# 08_FPGA_banks_3_4_5.net
KiCad netlist of a schematic drawn in Altium Designer
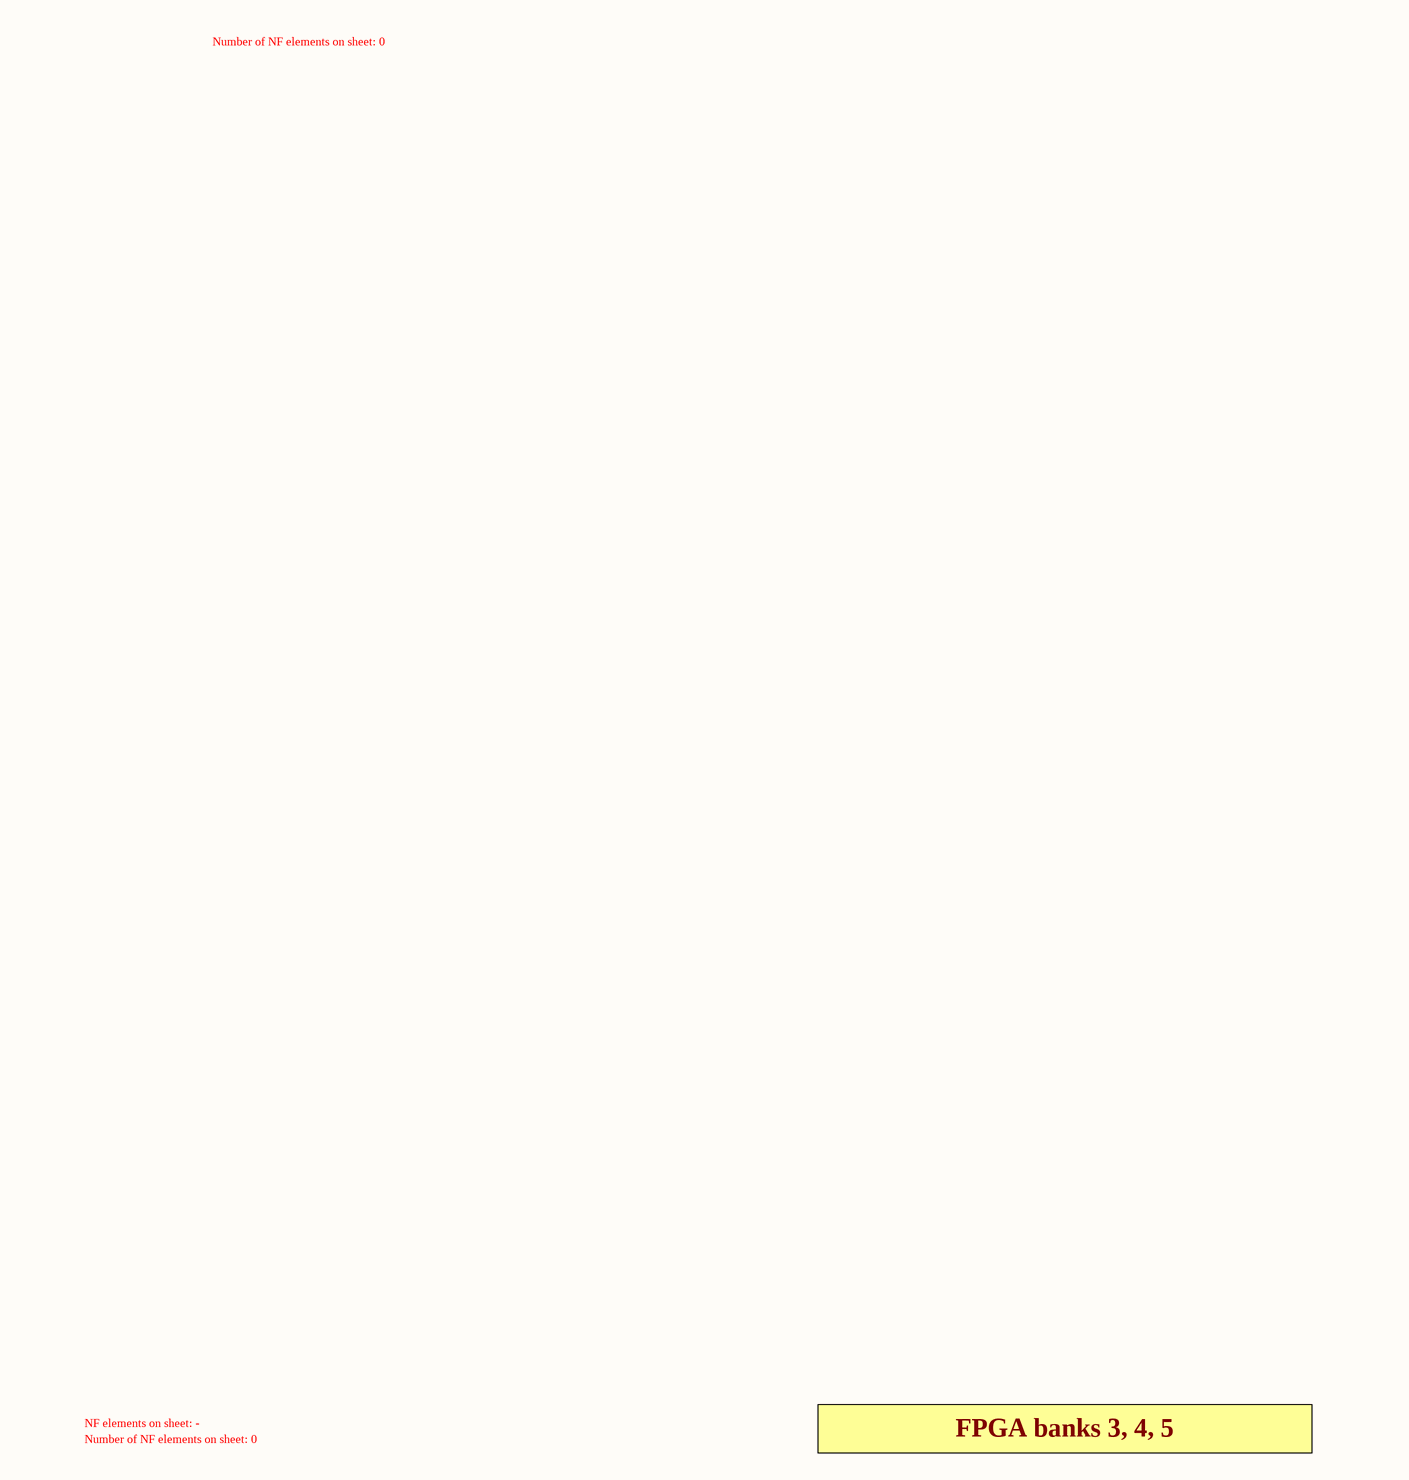
[diagram p0: 08_FPGA_banks_3_4_5.SchDoc, top]
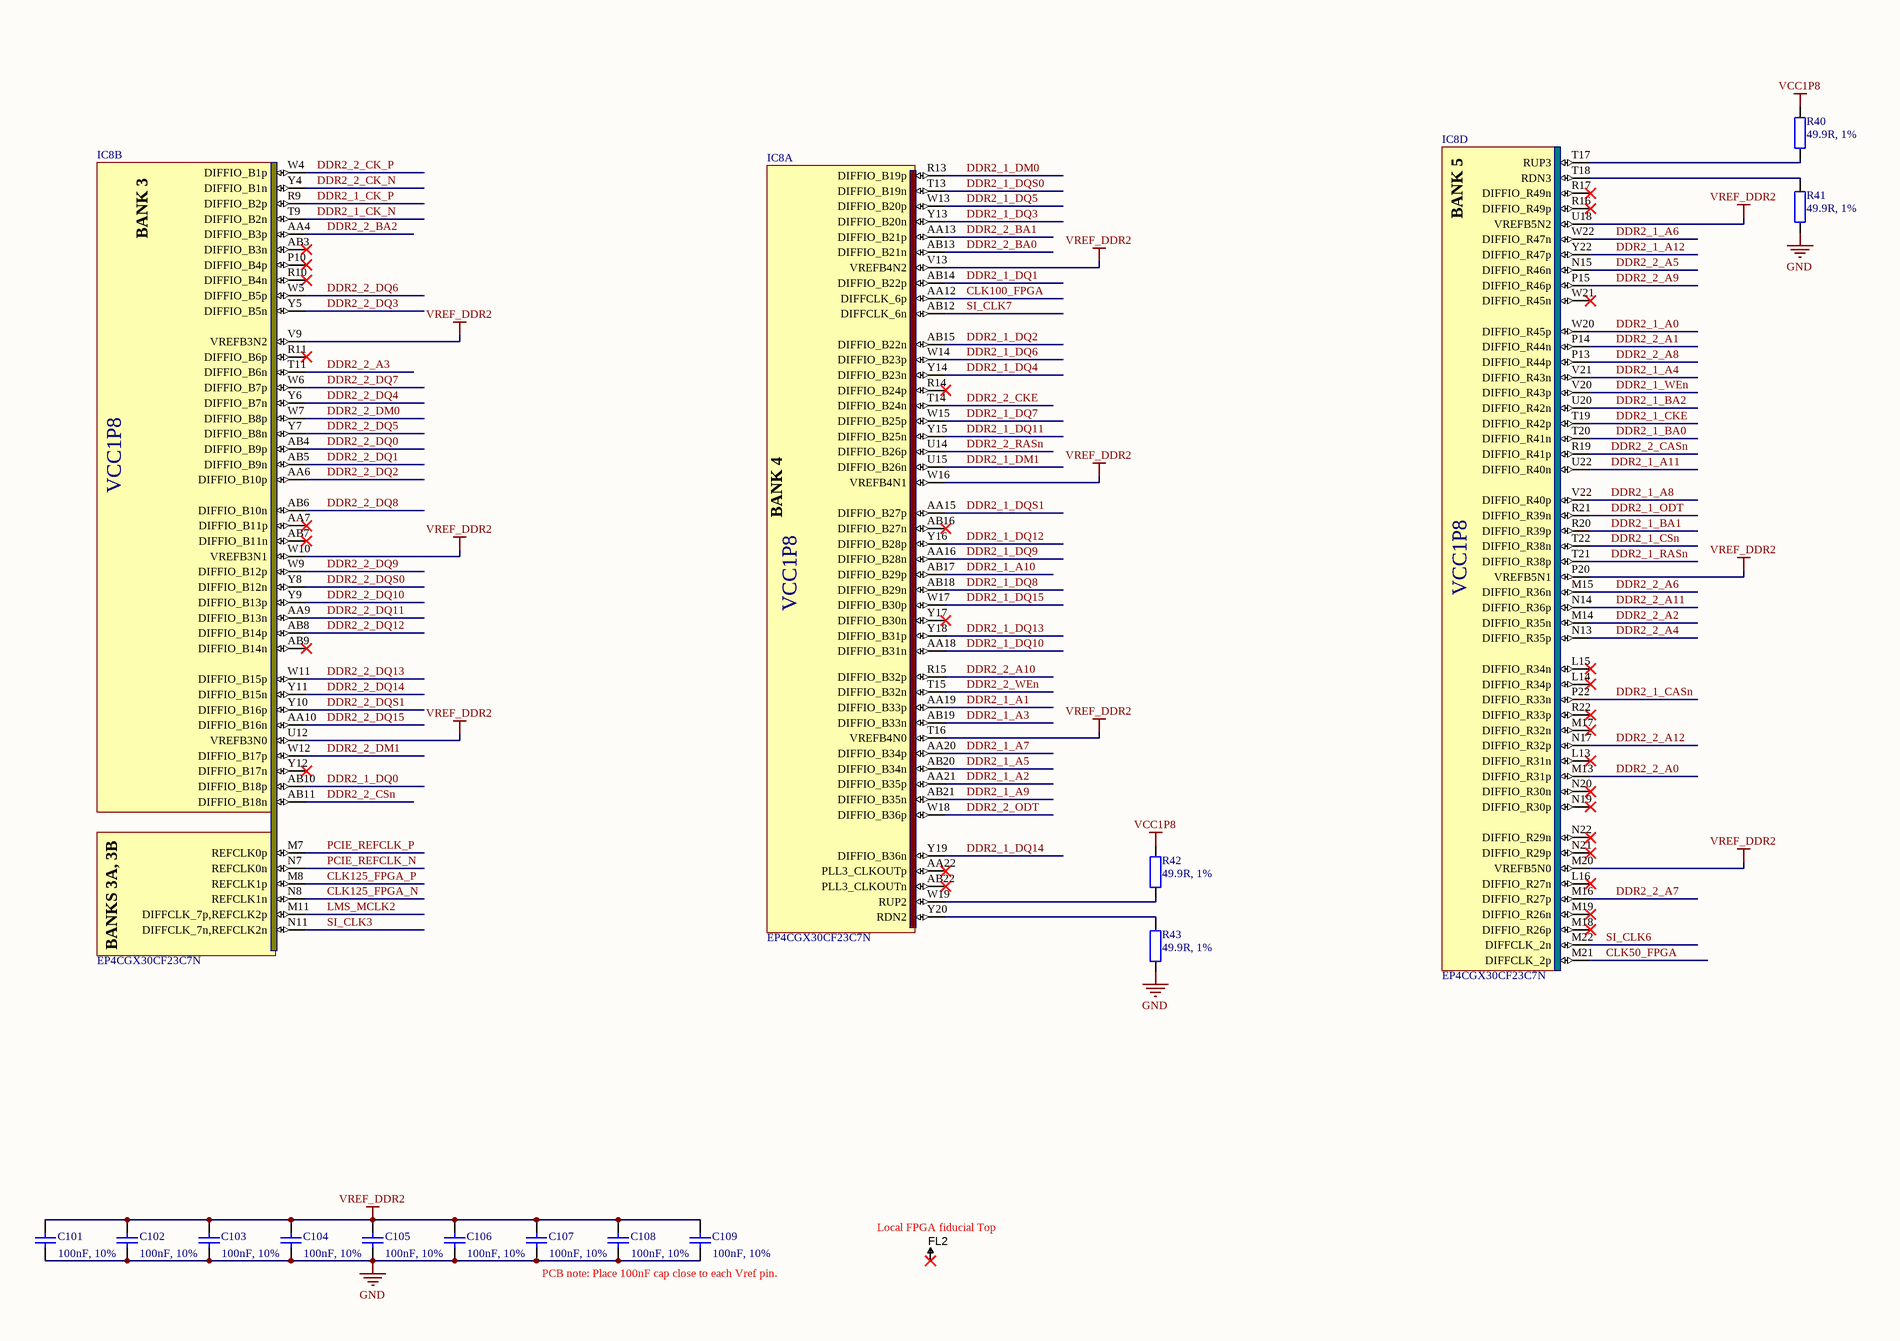
[diagram p1: 08_FPGA_banks_3_4_5.SchDoc, bottom]

(export (version "E")
  (design (tool "Eeschema 10.0.6"))
  (components
    (comp (ref "C101")
      (value "100nF, 10%")
      (footprint "CAP0402")
      (fields
        (field (name "TOLERANCE") "10 %")
        (field (name "MANUFACTURER") "Murata Electronics")
        (field (name "MANUFACTURER PART NUMBER") "GRM155R71C104KA88D")
      )
      (libsource (lib "LimeFPGAboard_schLib") (part "Cap_0603"))
    )
    (comp (ref "C102")
      (value "100nF, 10%")
      (footprint "CAP0402")
      (fields
        (field (name "TOLERANCE") "10 %")
        (field (name "MANUFACTURER") "Murata Electronics")
        (field (name "MANUFACTURER PART NUMBER") "GRM155R71C104KA88D")
      )
      (libsource (lib "LimeFPGAboard_schLib") (part "Cap_0603"))
    )
    (comp (ref "C103")
      (value "100nF, 10%")
      (footprint "CAP0402")
      (fields
        (field (name "TOLERANCE") "10 %")
        (field (name "MANUFACTURER") "Murata Electronics")
        (field (name "MANUFACTURER PART NUMBER") "GRM155R71C104KA88D")
      )
      (libsource (lib "LimeFPGAboard_schLib") (part "Cap_0603"))
    )
    (comp (ref "C104")
      (value "100nF, 10%")
      (footprint "CAP0402")
      (fields
        (field (name "TOLERANCE") "10 %")
        (field (name "MANUFACTURER") "Murata Electronics")
        (field (name "MANUFACTURER PART NUMBER") "GRM155R71C104KA88D")
      )
      (libsource (lib "LimeFPGAboard_schLib") (part "Cap_0603"))
    )
    (comp (ref "C105")
      (value "100nF, 10%")
      (footprint "CAP0402")
      (fields
        (field (name "TOLERANCE") "10 %")
        (field (name "MANUFACTURER") "Murata Electronics")
        (field (name "MANUFACTURER PART NUMBER") "GRM155R71C104KA88D")
      )
      (libsource (lib "LimeFPGAboard_schLib") (part "Cap_0603"))
    )
    (comp (ref "C106")
      (value "100nF, 10%")
      (footprint "CAP0402")
      (fields
        (field (name "TOLERANCE") "10 %")
        (field (name "MANUFACTURER") "Murata Electronics")
        (field (name "MANUFACTURER PART NUMBER") "GRM155R71C104KA88D")
      )
      (libsource (lib "LimeFPGAboard_schLib") (part "Cap_0603"))
    )
    (comp (ref "C107")
      (value "100nF, 10%")
      (footprint "CAP0402")
      (fields
        (field (name "TOLERANCE") "10 %")
        (field (name "MANUFACTURER") "Murata Electronics")
        (field (name "MANUFACTURER PART NUMBER") "GRM155R71C104KA88D")
      )
      (libsource (lib "LimeFPGAboard_schLib") (part "Cap_0603"))
    )
    (comp (ref "C108")
      (value "100nF, 10%")
      (footprint "CAP0402")
      (fields
        (field (name "TOLERANCE") "10 %")
        (field (name "MANUFACTURER") "Murata Electronics")
        (field (name "MANUFACTURER PART NUMBER") "GRM155R71C104KA88D")
      )
      (libsource (lib "LimeFPGAboard_schLib") (part "Cap_0603"))
    )
    (comp (ref "C109")
      (value "100nF, 10%")
      (footprint "CAP0402")
      (fields
        (field (name "TOLERANCE") "10 %")
        (field (name "MANUFACTURER") "Murata Electronics")
        (field (name "MANUFACTURER PART NUMBER") "GRM155R71C104KA88D")
      )
      (libsource (lib "LimeFPGAboard_schLib") (part "Cap_0603"))
    )
    (comp (ref "FL2")
      (value "Fiducial")
      (footprint "Fiducial_local")
      (libsource (lib "LimeMicroAltiumLib_schLib") (part "Fiducial"))
    )
    (comp (ref "IC8")
      (value "EP4CGX30CF23C7N")
      (footprint "ALTR-FBGA484_A-200")
      (fields (field (name "MANUFACTURER") "Altera"))
      (libsource (lib "LimeMicroAltiumLib_schLib") (part "EP4CGX30CF23C7N"))
    )
    (comp (ref "R40")
      (value "49.9R, 1%")
      (footprint "RES0402")
      (fields
        (field (name "TOLERANCE") "±1%")
        (field (name "MANUFACTURER") "Samsung Electro-Mechanics America, Inc.")
        (field (name "MANUFACTURER PART NUMBER") "RC1005F49R9CS")
      )
      (libsource (lib "LimeMicroAltiumLib_schLib") (part "Res_0402"))
    )
    (comp (ref "R41")
      (value "49.9R, 1%")
      (footprint "RES0402")
      (fields
        (field (name "TOLERANCE") "±1%")
        (field (name "MANUFACTURER") "Samsung Electro-Mechanics America, Inc.")
        (field (name "MANUFACTURER PART NUMBER") "RC1005F49R9CS")
      )
      (libsource (lib "LimeMicroAltiumLib_schLib") (part "Res_0402"))
    )
    (comp (ref "R42")
      (value "49.9R, 1%")
      (footprint "RES0402")
      (fields
        (field (name "TOLERANCE") "±1%")
        (field (name "MANUFACTURER") "Samsung Electro-Mechanics America, Inc.")
        (field (name "MANUFACTURER PART NUMBER") "RC1005F49R9CS")
      )
      (libsource (lib "LimeMicroAltiumLib_schLib") (part "Res_0402"))
    )
    (comp (ref "R43")
      (value "49.9R, 1%")
      (footprint "RES0402")
      (fields
        (field (name "TOLERANCE") "±1%")
        (field (name "MANUFACTURER") "Samsung Electro-Mechanics America, Inc.")
        (field (name "MANUFACTURER PART NUMBER") "RC1005F49R9CS")
      )
      (libsource (lib "LimeMicroAltiumLib_schLib") (part "Res_0402"))
    )
  )
  (nets
    (net (code "1") (name "/CLK50_FPGA") (class "Default")
      (node (ref "IC8") (pin "M21") (pinfunction "DIFFCLK_2p_M21") (pintype "bidirectional"))
    )
    (net (code "2") (name "/CLK100_FPGA") (class "Default")
      (node (ref "IC8") (pin "AA12") (pinfunction "DIFFCLK_6p_AA12") (pintype "bidirectional"))
    )
    (net (code "3") (name "/CLK125_FPGA_N") (class "Default")
      (node (ref "IC8") (pin "N8") (pinfunction "REFCLK1n_N8") (pintype "bidirectional"))
    )
    (net (code "4") (name "/CLK125_FPGA_P") (class "Default")
      (node (ref "IC8") (pin "M8") (pinfunction "REFCLK1p_M8") (pintype "bidirectional"))
    )
    (net (code "5") (name "/DDR2_1_A0") (class "Default")
      (node (ref "IC8") (pin "W20") (pinfunction "DIFFIO_R45p_W20") (pintype "bidirectional"))
    )
    (net (code "6") (name "/DDR2_1_A1") (class "Default")
      (node (ref "IC8") (pin "AA19") (pinfunction "DIFFIO_B33p_AA19") (pintype "bidirectional"))
    )
    (net (code "7") (name "/DDR2_1_A2") (class "Default")
      (node (ref "IC8") (pin "AA21") (pinfunction "DIFFIO_B35p_AA21") (pintype "bidirectional"))
    )
    (net (code "8") (name "/DDR2_1_A3") (class "Default")
      (node (ref "IC8") (pin "AB19") (pinfunction "DIFFIO_B33n_AB19") (pintype "bidirectional"))
    )
    (net (code "9") (name "/DDR2_1_A4") (class "Default")
      (node (ref "IC8") (pin "V21") (pinfunction "DIFFIO_R43n_V21") (pintype "bidirectional"))
    )
    (net (code "10") (name "/DDR2_1_A5") (class "Default")
      (node (ref "IC8") (pin "AB20") (pinfunction "DIFFIO_B34n_AB20") (pintype "bidirectional"))
    )
    (net (code "11") (name "/DDR2_1_A6") (class "Default")
      (node (ref "IC8") (pin "W22") (pinfunction "DIFFIO_R47n_W22") (pintype "bidirectional"))
    )
    (net (code "12") (name "/DDR2_1_A7") (class "Default")
      (node (ref "IC8") (pin "AA20") (pinfunction "DIFFIO_B34p_AA20") (pintype "bidirectional"))
    )
    (net (code "13") (name "/DDR2_1_A8") (class "Default")
      (node (ref "IC8") (pin "V22") (pinfunction "DIFFIO_R40p_V22") (pintype "bidirectional"))
    )
    (net (code "14") (name "/DDR2_1_A9") (class "Default")
      (node (ref "IC8") (pin "AB21") (pinfunction "DIFFIO_B35n_AB21") (pintype "bidirectional"))
    )
    (net (code "15") (name "/DDR2_1_A10") (class "Default")
      (node (ref "IC8") (pin "AB17") (pinfunction "DIFFIO_B29p_AB17") (pintype "bidirectional"))
    )
    (net (code "16") (name "/DDR2_1_A11") (class "Default")
      (node (ref "IC8") (pin "U22") (pinfunction "DIFFIO_R40n_U22") (pintype "bidirectional"))
    )
    (net (code "17") (name "/DDR2_1_A12") (class "Default")
      (node (ref "IC8") (pin "Y22") (pinfunction "DIFFIO_R47p_Y22") (pintype "bidirectional"))
    )
    (net (code "18") (name "/DDR2_1_BA0") (class "Default")
      (node (ref "IC8") (pin "T20") (pinfunction "DIFFIO_R41n_T20") (pintype "bidirectional"))
    )
    (net (code "19") (name "/DDR2_1_BA1") (class "Default")
      (node (ref "IC8") (pin "R20") (pinfunction "DIFFIO_R39p_R20") (pintype "bidirectional"))
    )
    (net (code "20") (name "/DDR2_1_BA2") (class "Default")
      (node (ref "IC8") (pin "U20") (pinfunction "DIFFIO_R42n_U20") (pintype "bidirectional"))
    )
    (net (code "21") (name "/DDR2_1_CASn") (class "Default")
      (node (ref "IC8") (pin "P22") (pinfunction "DIFFIO_R33n_P22") (pintype "bidirectional"))
    )
    (net (code "22") (name "/DDR2_1_CKE") (class "Default")
      (node (ref "IC8") (pin "T19") (pinfunction "DIFFIO_R42p_T19") (pintype "bidirectional"))
    )
    (net (code "23") (name "/DDR2_1_CK_N") (class "Default")
      (node (ref "IC8") (pin "T9") (pinfunction "DIFFIO_B2n_T9") (pintype "bidirectional"))
    )
    (net (code "24") (name "/DDR2_1_CK_P") (class "Default")
      (node (ref "IC8") (pin "R9") (pinfunction "DIFFIO_B2p_R9") (pintype "bidirectional"))
    )
    (net (code "25") (name "/DDR2_1_CSn") (class "Default")
      (node (ref "IC8") (pin "T22") (pinfunction "DIFFIO_R38n_T22") (pintype "bidirectional"))
    )
    (net (code "26") (name "/DDR2_1_DM0") (class "Default")
      (node (ref "IC8") (pin "R13") (pinfunction "DIFFIO_B19p_R13") (pintype "bidirectional"))
    )
    (net (code "27") (name "/DDR2_1_DM1") (class "Default")
      (node (ref "IC8") (pin "U15") (pinfunction "DIFFIO_B26n_U15") (pintype "bidirectional"))
    )
    (net (code "28") (name "/DDR2_1_DQ0") (class "Default")
      (node (ref "IC8") (pin "AB10") (pinfunction "DIFFIO_B18p_AB10") (pintype "bidirectional"))
    )
    (net (code "29") (name "/DDR2_1_DQ1") (class "Default")
      (node (ref "IC8") (pin "AB14") (pinfunction "DIFFIO_B22p_AB14") (pintype "bidirectional"))
    )
    (net (code "30") (name "/DDR2_1_DQ2") (class "Default")
      (node (ref "IC8") (pin "AB15") (pinfunction "DIFFIO_B22n_AB15") (pintype "bidirectional"))
    )
    (net (code "31") (name "/DDR2_1_DQ3") (class "Default")
      (node (ref "IC8") (pin "Y13") (pinfunction "DIFFIO_B20n_Y13") (pintype "bidirectional"))
    )
    (net (code "32") (name "/DDR2_1_DQ4") (class "Default")
      (node (ref "IC8") (pin "Y14") (pinfunction "DIFFIO_B23n_Y14") (pintype "bidirectional"))
    )
    (net (code "33") (name "/DDR2_1_DQ5") (class "Default")
      (node (ref "IC8") (pin "W13") (pinfunction "DIFFIO_B20p_W13") (pintype "bidirectional"))
    )
    (net (code "34") (name "/DDR2_1_DQ6") (class "Default")
      (node (ref "IC8") (pin "W14") (pinfunction "DIFFIO_B23p_W14") (pintype "bidirectional"))
    )
    (net (code "35") (name "/DDR2_1_DQ7") (class "Default")
      (node (ref "IC8") (pin "W15") (pinfunction "DIFFIO_B25p_W15") (pintype "bidirectional"))
    )
    (net (code "36") (name "/DDR2_1_DQ8") (class "Default")
      (node (ref "IC8") (pin "AB18") (pinfunction "DIFFIO_B29n_AB18") (pintype "bidirectional"))
    )
    (net (code "37") (name "/DDR2_1_DQ9") (class "Default")
      (node (ref "IC8") (pin "AA16") (pinfunction "DIFFIO_B28n_AA16") (pintype "bidirectional"))
    )
    (net (code "38") (name "/DDR2_1_DQ10") (class "Default")
      (node (ref "IC8") (pin "AA18") (pinfunction "DIFFIO_B31n_AA18") (pintype "bidirectional"))
    )
    (net (code "39") (name "/DDR2_1_DQ11") (class "Default")
      (node (ref "IC8") (pin "Y15") (pinfunction "DIFFIO_B25n_Y15") (pintype "bidirectional"))
    )
    (net (code "40") (name "/DDR2_1_DQ12") (class "Default")
      (node (ref "IC8") (pin "Y16") (pinfunction "DIFFIO_B28p_Y16") (pintype "bidirectional"))
    )
    (net (code "41") (name "/DDR2_1_DQ13") (class "Default")
      (node (ref "IC8") (pin "Y18") (pinfunction "DIFFIO_B31p_Y18") (pintype "bidirectional"))
    )
    (net (code "42") (name "/DDR2_1_DQ14") (class "Default")
      (node (ref "IC8") (pin "Y19") (pinfunction "DIFFIO_B36n_Y19") (pintype "bidirectional"))
    )
    (net (code "43") (name "/DDR2_1_DQ15") (class "Default")
      (node (ref "IC8") (pin "W17") (pinfunction "DIFFIO_B30p_W17") (pintype "bidirectional"))
    )
    (net (code "44") (name "/DDR2_1_DQS0") (class "Default")
      (node (ref "IC8") (pin "T13") (pinfunction "DIFFIO_B19n_T13") (pintype "bidirectional"))
    )
    (net (code "45") (name "/DDR2_1_DQS1") (class "Default")
      (node (ref "IC8") (pin "AA15") (pinfunction "DIFFIO_B27p_AA15") (pintype "bidirectional"))
    )
    (net (code "46") (name "/DDR2_1_ODT") (class "Default")
      (node (ref "IC8") (pin "R21") (pinfunction "DIFFIO_R39n_R21") (pintype "bidirectional"))
    )
    (net (code "47") (name "/DDR2_1_RASn") (class "Default")
      (node (ref "IC8") (pin "T21") (pinfunction "DIFFIO_R38p_T21") (pintype "bidirectional"))
    )
    (net (code "48") (name "/DDR2_1_WEn") (class "Default")
      (node (ref "IC8") (pin "V20") (pinfunction "DIFFIO_R43p_V20") (pintype "bidirectional"))
    )
    (net (code "49") (name "/DDR2_2_A0") (class "Default")
      (node (ref "IC8") (pin "M13") (pinfunction "DIFFIO_R31p_M13") (pintype "bidirectional"))
    )
    (net (code "50") (name "/DDR2_2_A1") (class "Default")
      (node (ref "IC8") (pin "P14") (pinfunction "DIFFIO_R44n_P14") (pintype "bidirectional"))
    )
    (net (code "51") (name "/DDR2_2_A2") (class "Default")
      (node (ref "IC8") (pin "M14") (pinfunction "DIFFIO_R35n_M14") (pintype "bidirectional"))
    )
    (net (code "52") (name "/DDR2_2_A3") (class "Default")
      (node (ref "IC8") (pin "T11") (pinfunction "DIFFIO_B6n_T11") (pintype "bidirectional"))
    )
    (net (code "53") (name "/DDR2_2_A4") (class "Default")
      (node (ref "IC8") (pin "N13") (pinfunction "DIFFIO_R35p_N13") (pintype "bidirectional"))
    )
    (net (code "54") (name "/DDR2_2_A5") (class "Default")
      (node (ref "IC8") (pin "N15") (pinfunction "DIFFIO_R46n_N15") (pintype "bidirectional"))
    )
    (net (code "55") (name "/DDR2_2_A6") (class "Default")
      (node (ref "IC8") (pin "M15") (pinfunction "DIFFIO_R36n_M15") (pintype "bidirectional"))
    )
    (net (code "56") (name "/DDR2_2_A7") (class "Default")
      (node (ref "IC8") (pin "M16") (pinfunction "DIFFIO_R27p_M16") (pintype "bidirectional"))
    )
    (net (code "57") (name "/DDR2_2_A8") (class "Default")
      (node (ref "IC8") (pin "P13") (pinfunction "DIFFIO_R44p_P13") (pintype "bidirectional"))
    )
    (net (code "58") (name "/DDR2_2_A9") (class "Default")
      (node (ref "IC8") (pin "P15") (pinfunction "DIFFIO_R46p_P15") (pintype "bidirectional"))
    )
    (net (code "59") (name "/DDR2_2_A10") (class "Default")
      (node (ref "IC8") (pin "R15") (pinfunction "DIFFIO_B32p_R15") (pintype "bidirectional"))
    )
    (net (code "60") (name "/DDR2_2_A11") (class "Default")
      (node (ref "IC8") (pin "N14") (pinfunction "DIFFIO_R36p_N14") (pintype "bidirectional"))
    )
    (net (code "61") (name "/DDR2_2_A12") (class "Default")
      (node (ref "IC8") (pin "N17") (pinfunction "DIFFIO_R32p_N17") (pintype "bidirectional"))
    )
    (net (code "62") (name "/DDR2_2_BA0") (class "Default")
      (node (ref "IC8") (pin "AB13") (pinfunction "DIFFIO_B21n_AB13") (pintype "bidirectional"))
    )
    (net (code "63") (name "/DDR2_2_BA1") (class "Default")
      (node (ref "IC8") (pin "AA13") (pinfunction "DIFFIO_B21p_AA13") (pintype "bidirectional"))
    )
    (net (code "64") (name "/DDR2_2_BA2") (class "Default")
      (node (ref "IC8") (pin "AA4") (pinfunction "DIFFIO_B3p_AA4") (pintype "bidirectional"))
    )
    (net (code "65") (name "/DDR2_2_CASn") (class "Default")
      (node (ref "IC8") (pin "R19") (pinfunction "DIFFIO_R41p_R19") (pintype "bidirectional"))
    )
    (net (code "66") (name "/DDR2_2_CKE") (class "Default")
      (node (ref "IC8") (pin "T14") (pinfunction "DIFFIO_B24n_T14") (pintype "bidirectional"))
    )
    (net (code "67") (name "/DDR2_2_CK_N") (class "Default")
      (node (ref "IC8") (pin "Y4") (pinfunction "DIFFIO_B1n_Y4") (pintype "bidirectional"))
    )
    (net (code "68") (name "/DDR2_2_CK_P") (class "Default")
      (node (ref "IC8") (pin "W4") (pinfunction "DIFFIO_B1p_W4") (pintype "bidirectional"))
    )
    (net (code "69") (name "/DDR2_2_CSn") (class "Default")
      (node (ref "IC8") (pin "AB11") (pinfunction "DIFFIO_B18n_AB11") (pintype "bidirectional"))
    )
    (net (code "70") (name "/DDR2_2_DM0") (class "Default")
      (node (ref "IC8") (pin "W7") (pinfunction "DIFFIO_B8p_W7") (pintype "bidirectional"))
    )
    (net (code "71") (name "/DDR2_2_DM1") (class "Default")
      (node (ref "IC8") (pin "W12") (pinfunction "DIFFIO_B17p_W12") (pintype "bidirectional"))
    )
    (net (code "72") (name "/DDR2_2_DQ0") (class "Default")
      (node (ref "IC8") (pin "AB4") (pinfunction "DIFFIO_B9p_AB4") (pintype "bidirectional"))
    )
    (net (code "73") (name "/DDR2_2_DQ1") (class "Default")
      (node (ref "IC8") (pin "AB5") (pinfunction "DIFFIO_B9n_AB5") (pintype "bidirectional"))
    )
    (net (code "74") (name "/DDR2_2_DQ2") (class "Default")
      (node (ref "IC8") (pin "AA6") (pinfunction "DIFFIO_B10p_AA6") (pintype "bidirectional"))
    )
    (net (code "75") (name "/DDR2_2_DQ3") (class "Default")
      (node (ref "IC8") (pin "Y5") (pinfunction "DIFFIO_B5n_Y5") (pintype "bidirectional"))
    )
    (net (code "76") (name "/DDR2_2_DQ4") (class "Default")
      (node (ref "IC8") (pin "Y6") (pinfunction "DIFFIO_B7n_Y6") (pintype "bidirectional"))
    )
    (net (code "77") (name "/DDR2_2_DQ5") (class "Default")
      (node (ref "IC8") (pin "Y7") (pinfunction "DIFFIO_B8n_Y7") (pintype "bidirectional"))
    )
    (net (code "78") (name "/DDR2_2_DQ6") (class "Default")
      (node (ref "IC8") (pin "W5") (pinfunction "DIFFIO_B5p_W5") (pintype "bidirectional"))
    )
    (net (code "79") (name "/DDR2_2_DQ7") (class "Default")
      (node (ref "IC8") (pin "W6") (pinfunction "DIFFIO_B7p_W6") (pintype "bidirectional"))
    )
    (net (code "80") (name "/DDR2_2_DQ8") (class "Default")
      (node (ref "IC8") (pin "AB6") (pinfunction "DIFFIO_B10n_AB6") (pintype "bidirectional"))
    )
    (net (code "81") (name "/DDR2_2_DQ9") (class "Default")
      (node (ref "IC8") (pin "W9") (pinfunction "DIFFIO_B12p_W9") (pintype "bidirectional"))
    )
    (net (code "82") (name "/DDR2_2_DQ10") (class "Default")
      (node (ref "IC8") (pin "Y9") (pinfunction "DIFFIO_B13p_Y9") (pintype "bidirectional"))
    )
    (net (code "83") (name "/DDR2_2_DQ11") (class "Default")
      (node (ref "IC8") (pin "AA9") (pinfunction "DIFFIO_B13n_AA9") (pintype "bidirectional"))
    )
    (net (code "84") (name "/DDR2_2_DQ12") (class "Default")
      (node (ref "IC8") (pin "AB8") (pinfunction "DIFFIO_B14p_AB8") (pintype "bidirectional"))
    )
    (net (code "85") (name "/DDR2_2_DQ13") (class "Default")
      (node (ref "IC8") (pin "W11") (pinfunction "DIFFIO_B15p_W11") (pintype "bidirectional"))
    )
    (net (code "86") (name "/DDR2_2_DQ14") (class "Default")
      (node (ref "IC8") (pin "Y11") (pinfunction "DIFFIO_B15n_Y11") (pintype "bidirectional"))
    )
    (net (code "87") (name "/DDR2_2_DQ15") (class "Default")
      (node (ref "IC8") (pin "AA10") (pinfunction "DIFFIO_B16n_AA10") (pintype "bidirectional"))
    )
    (net (code "88") (name "/DDR2_2_DQS0") (class "Default")
      (node (ref "IC8") (pin "Y8") (pinfunction "DIFFIO_B12n_Y8") (pintype "bidirectional"))
    )
    (net (code "89") (name "/DDR2_2_DQS1") (class "Default")
      (node (ref "IC8") (pin "Y10") (pinfunction "DIFFIO_B16p_Y10") (pintype "bidirectional"))
    )
    (net (code "90") (name "/DDR2_2_ODT") (class "Default")
      (node (ref "IC8") (pin "W18") (pinfunction "DIFFIO_B36p_W18") (pintype "bidirectional"))
    )
    (net (code "91") (name "/DDR2_2_RASn") (class "Default")
      (node (ref "IC8") (pin "U14") (pinfunction "DIFFIO_B26p_U14") (pintype "bidirectional"))
    )
    (net (code "92") (name "/DDR2_2_WEn") (class "Default")
      (node (ref "IC8") (pin "T15") (pinfunction "DIFFIO_B32n_T15") (pintype "bidirectional"))
    )
    (net (code "93") (name "/LMS_MCLK2") (class "Default")
      (node (ref "IC8") (pin "M11") (pinfunction "DIFFCLK_7p,REFCLK2p_M11") (pintype "bidirectional"))
    )
    (net (code "94") (name "/PCIE_REFCLK_N") (class "Default")
      (node (ref "IC8") (pin "N7") (pinfunction "REFCLK0n_N7") (pintype "bidirectional"))
    )
    (net (code "95") (name "/PCIE_REFCLK_P") (class "Default")
      (node (ref "IC8") (pin "M7") (pinfunction "REFCLK0p_M7") (pintype "bidirectional"))
    )
    (net (code "96") (name "/SI_CLK3") (class "Default")
      (node (ref "IC8") (pin "N11") (pinfunction "DIFFCLK_7n,REFCLK2n_N11") (pintype "bidirectional"))
    )
    (net (code "97") (name "/SI_CLK6") (class "Default")
      (node (ref "IC8") (pin "M22") (pinfunction "DIFFCLK_2n_M22") (pintype "bidirectional"))
    )
    (net (code "98") (name "/SI_CLK7") (class "Default")
      (node (ref "IC8") (pin "AB12") (pinfunction "DIFFCLK_6n_AB12") (pintype "bidirectional"))
    )
    (net (code "99") (name "GND") (class "Default")
      (node (ref "C101") (pin "2") (pinfunction "2_2") (pintype "passive"))
      (node (ref "C102") (pin "2") (pinfunction "2_2") (pintype "passive"))
      (node (ref "C103") (pin "2") (pinfunction "2_2") (pintype "passive"))
      (node (ref "C104") (pin "2") (pinfunction "2_2") (pintype "passive"))
      (node (ref "C105") (pin "2") (pinfunction "2_2") (pintype "passive"))
      (node (ref "C106") (pin "2") (pinfunction "2_2") (pintype "passive"))
      (node (ref "C107") (pin "2") (pinfunction "2_2") (pintype "passive"))
      (node (ref "C108") (pin "2") (pinfunction "2_2") (pintype "passive"))
      (node (ref "C109") (pin "2") (pinfunction "2_2") (pintype "passive"))
      (node (ref "R41") (pin "1") (pinfunction "1_1") (pintype "passive"))
      (node (ref "R43") (pin "1") (pinfunction "1_1") (pintype "passive"))
    )
    (net (code "100") (name "Net-(IC8A-RDN2)") (class "Default")
      (node (ref "IC8") (pin "Y20") (pinfunction "RDN2_Y20") (pintype "bidirectional"))
      (node (ref "R43") (pin "2") (pinfunction "2_2") (pintype "passive"))
    )
    (net (code "101") (name "Net-(IC8A-RUP2)") (class "Default")
      (node (ref "IC8") (pin "W19") (pinfunction "RUP2_W19") (pintype "bidirectional"))
      (node (ref "R42") (pin "1") (pinfunction "1_1") (pintype "passive"))
    )
    (net (code "102") (name "Net-(IC8D-RDN3)") (class "Default")
      (node (ref "IC8") (pin "T18") (pinfunction "RDN3_T18") (pintype "bidirectional"))
      (node (ref "R41") (pin "2") (pinfunction "2_2") (pintype "passive"))
    )
    (net (code "103") (name "Net-(IC8D-RUP3)") (class "Default")
      (node (ref "IC8") (pin "T17") (pinfunction "RUP3_T17") (pintype "bidirectional"))
      (node (ref "R40") (pin "1") (pinfunction "1_1") (pintype "passive"))
    )
    (net (code "104") (name "VCC1P8") (class "Default")
      (node (ref "R40") (pin "2") (pinfunction "2_2") (pintype "passive"))
      (node (ref "R42") (pin "2") (pinfunction "2_2") (pintype "passive"))
    )
    (net (code "105") (name "VREF_DDR2") (class "Default")
      (node (ref "C101") (pin "1") (pinfunction "1_1") (pintype "passive"))
      (node (ref "C102") (pin "1") (pinfunction "1_1") (pintype "passive"))
      (node (ref "C103") (pin "1") (pinfunction "1_1") (pintype "passive"))
      (node (ref "C104") (pin "1") (pinfunction "1_1") (pintype "passive"))
      (node (ref "C105") (pin "1") (pinfunction "1_1") (pintype "passive"))
      (node (ref "C106") (pin "1") (pinfunction "1_1") (pintype "passive"))
      (node (ref "C107") (pin "1") (pinfunction "1_1") (pintype "passive"))
      (node (ref "C108") (pin "1") (pinfunction "1_1") (pintype "passive"))
      (node (ref "C109") (pin "1") (pinfunction "1_1") (pintype "passive"))
      (node (ref "IC8") (pin "M20") (pinfunction "VREFB5N0_M20") (pintype "bidirectional"))
      (node (ref "IC8") (pin "P20") (pinfunction "VREFB5N1_P20") (pintype "bidirectional"))
      (node (ref "IC8") (pin "T16") (pinfunction "VREFB4N0_T16") (pintype "bidirectional"))
      (node (ref "IC8") (pin "U12") (pinfunction "VREFB3N0_U12") (pintype "bidirectional"))
      (node (ref "IC8") (pin "U18") (pinfunction "VREFB5N2_U18") (pintype "bidirectional"))
      (node (ref "IC8") (pin "V13") (pinfunction "VREFB4N2_V13") (pintype "bidirectional"))
      (node (ref "IC8") (pin "V9") (pinfunction "VREFB3N2_V9") (pintype "bidirectional"))
      (node (ref "IC8") (pin "W10") (pinfunction "VREFB3N1_W10") (pintype "bidirectional"))
      (node (ref "IC8") (pin "W16") (pinfunction "VREFB4N1_W16") (pintype "bidirectional"))
    )
    (net (code "106") (name "unconnected-(FL2-Pad1)") (class "Default")
      (node (ref "FL2") (pin "1") (pintype "passive+no_connect"))
    )
    (net (code "107") (name "unconnected-(IC8A-DIFFIO_B24p-PadR14)") (class "Default")
      (node (ref "IC8") (pin "R14") (pinfunction "DIFFIO_B24p_R14") (pintype "bidirectional+no_connect"))
    )
    (net (code "108") (name "unconnected-(IC8A-DIFFIO_B27n-PadAB16)") (class "Default")
      (node (ref "IC8") (pin "AB16") (pinfunction "DIFFIO_B27n_AB16") (pintype "bidirectional+no_connect"))
    )
    (net (code "109") (name "unconnected-(IC8A-DIFFIO_B30n-PadY17)") (class "Default")
      (node (ref "IC8") (pin "Y17") (pinfunction "DIFFIO_B30n_Y17") (pintype "bidirectional+no_connect"))
    )
    (net (code "110") (name "unconnected-(IC8A-PLL3_CLKOUTn-PadAB22)") (class "Default")
      (node (ref "IC8") (pin "AB22") (pinfunction "PLL3_CLKOUTn_AB22") (pintype "bidirectional+no_connect"))
    )
    (net (code "111") (name "unconnected-(IC8A-PLL3_CLKOUTp-PadAA22)") (class "Default")
      (node (ref "IC8") (pin "AA22") (pinfunction "PLL3_CLKOUTp_AA22") (pintype "bidirectional+no_connect"))
    )
    (net (code "112") (name "unconnected-(IC8B-DIFFIO_B3n-PadAB3)") (class "Default")
      (node (ref "IC8") (pin "AB3") (pinfunction "DIFFIO_B3n_AB3") (pintype "bidirectional+no_connect"))
    )
    (net (code "113") (name "unconnected-(IC8B-DIFFIO_B4n-PadR10)") (class "Default")
      (node (ref "IC8") (pin "R10") (pinfunction "DIFFIO_B4n_R10") (pintype "bidirectional+no_connect"))
    )
    (net (code "114") (name "unconnected-(IC8B-DIFFIO_B4p-PadP10)") (class "Default")
      (node (ref "IC8") (pin "P10") (pinfunction "DIFFIO_B4p_P10") (pintype "bidirectional+no_connect"))
    )
    (net (code "115") (name "unconnected-(IC8B-DIFFIO_B6p-PadR11)") (class "Default")
      (node (ref "IC8") (pin "R11") (pinfunction "DIFFIO_B6p_R11") (pintype "bidirectional+no_connect"))
    )
    (net (code "116") (name "unconnected-(IC8B-DIFFIO_B11n-PadAB7)") (class "Default")
      (node (ref "IC8") (pin "AB7") (pinfunction "DIFFIO_B11n_AB7") (pintype "bidirectional+no_connect"))
    )
    (net (code "117") (name "unconnected-(IC8B-DIFFIO_B11p-PadAA7)") (class "Default")
      (node (ref "IC8") (pin "AA7") (pinfunction "DIFFIO_B11p_AA7") (pintype "bidirectional+no_connect"))
    )
    (net (code "118") (name "unconnected-(IC8B-DIFFIO_B14n-PadAB9)") (class "Default")
      (node (ref "IC8") (pin "AB9") (pinfunction "DIFFIO_B14n_AB9") (pintype "bidirectional+no_connect"))
    )
    (net (code "119") (name "unconnected-(IC8B-DIFFIO_B17n-PadY12)") (class "Default")
      (node (ref "IC8") (pin "Y12") (pinfunction "DIFFIO_B17n_Y12") (pintype "bidirectional+no_connect"))
    )
    (net (code "120") (name "unconnected-(IC8D-DIFFIO_R26n-PadM19)") (class "Default")
      (node (ref "IC8") (pin "M19") (pinfunction "DIFFIO_R26n_M19") (pintype "bidirectional+no_connect"))
    )
    (net (code "121") (name "unconnected-(IC8D-DIFFIO_R26p-PadM18)") (class "Default")
      (node (ref "IC8") (pin "M18") (pinfunction "DIFFIO_R26p_M18") (pintype "bidirectional+no_connect"))
    )
    (net (code "122") (name "unconnected-(IC8D-DIFFIO_R27n-PadL16)") (class "Default")
      (node (ref "IC8") (pin "L16") (pinfunction "DIFFIO_R27n_L16") (pintype "bidirectional+no_connect"))
    )
    (net (code "123") (name "unconnected-(IC8D-DIFFIO_R29n-PadN22)") (class "Default")
      (node (ref "IC8") (pin "N22") (pinfunction "DIFFIO_R29n_N22") (pintype "bidirectional+no_connect"))
    )
    (net (code "124") (name "unconnected-(IC8D-DIFFIO_R29p-PadN21)") (class "Default")
      (node (ref "IC8") (pin "N21") (pinfunction "DIFFIO_R29p_N21") (pintype "bidirectional+no_connect"))
    )
    (net (code "125") (name "unconnected-(IC8D-DIFFIO_R30n-PadN20)") (class "Default")
      (node (ref "IC8") (pin "N20") (pinfunction "DIFFIO_R30n_N20") (pintype "bidirectional+no_connect"))
    )
    (net (code "126") (name "unconnected-(IC8D-DIFFIO_R30p-PadN19)") (class "Default")
      (node (ref "IC8") (pin "N19") (pinfunction "DIFFIO_R30p_N19") (pintype "bidirectional+no_connect"))
    )
    (net (code "127") (name "unconnected-(IC8D-DIFFIO_R31n-PadL13)") (class "Default")
      (node (ref "IC8") (pin "L13") (pinfunction "DIFFIO_R31n_L13") (pintype "bidirectional+no_connect"))
    )
    (net (code "128") (name "unconnected-(IC8D-DIFFIO_R32n-PadM17)") (class "Default")
      (node (ref "IC8") (pin "M17") (pinfunction "DIFFIO_R32n_M17") (pintype "bidirectional+no_connect"))
    )
    (net (code "129") (name "unconnected-(IC8D-DIFFIO_R33p-PadR22)") (class "Default")
      (node (ref "IC8") (pin "R22") (pinfunction "DIFFIO_R33p_R22") (pintype "bidirectional+no_connect"))
    )
    (net (code "130") (name "unconnected-(IC8D-DIFFIO_R34n-PadL15)") (class "Default")
      (node (ref "IC8") (pin "L15") (pinfunction "DIFFIO_R34n_L15") (pintype "bidirectional+no_connect"))
    )
    (net (code "131") (name "unconnected-(IC8D-DIFFIO_R34p-PadL14)") (class "Default")
      (node (ref "IC8") (pin "L14") (pinfunction "DIFFIO_R34p_L14") (pintype "bidirectional+no_connect"))
    )
    (net (code "132") (name "unconnected-(IC8D-DIFFIO_R45n-PadW21)") (class "Default")
      (node (ref "IC8") (pin "W21") (pinfunction "DIFFIO_R45n_W21") (pintype "bidirectional+no_connect"))
    )
    (net (code "133") (name "unconnected-(IC8D-DIFFIO_R49n-PadR17)") (class "Default")
      (node (ref "IC8") (pin "R17") (pinfunction "DIFFIO_R49n_R17") (pintype "bidirectional+no_connect"))
    )
    (net (code "134") (name "unconnected-(IC8D-DIFFIO_R49p-PadR16)") (class "Default")
      (node (ref "IC8") (pin "R16") (pinfunction "DIFFIO_R49p_R16") (pintype "bidirectional+no_connect"))
    )
  )
)
